# LoRaPi.net
KiCad netlist of a schematic drawn in EAGLE
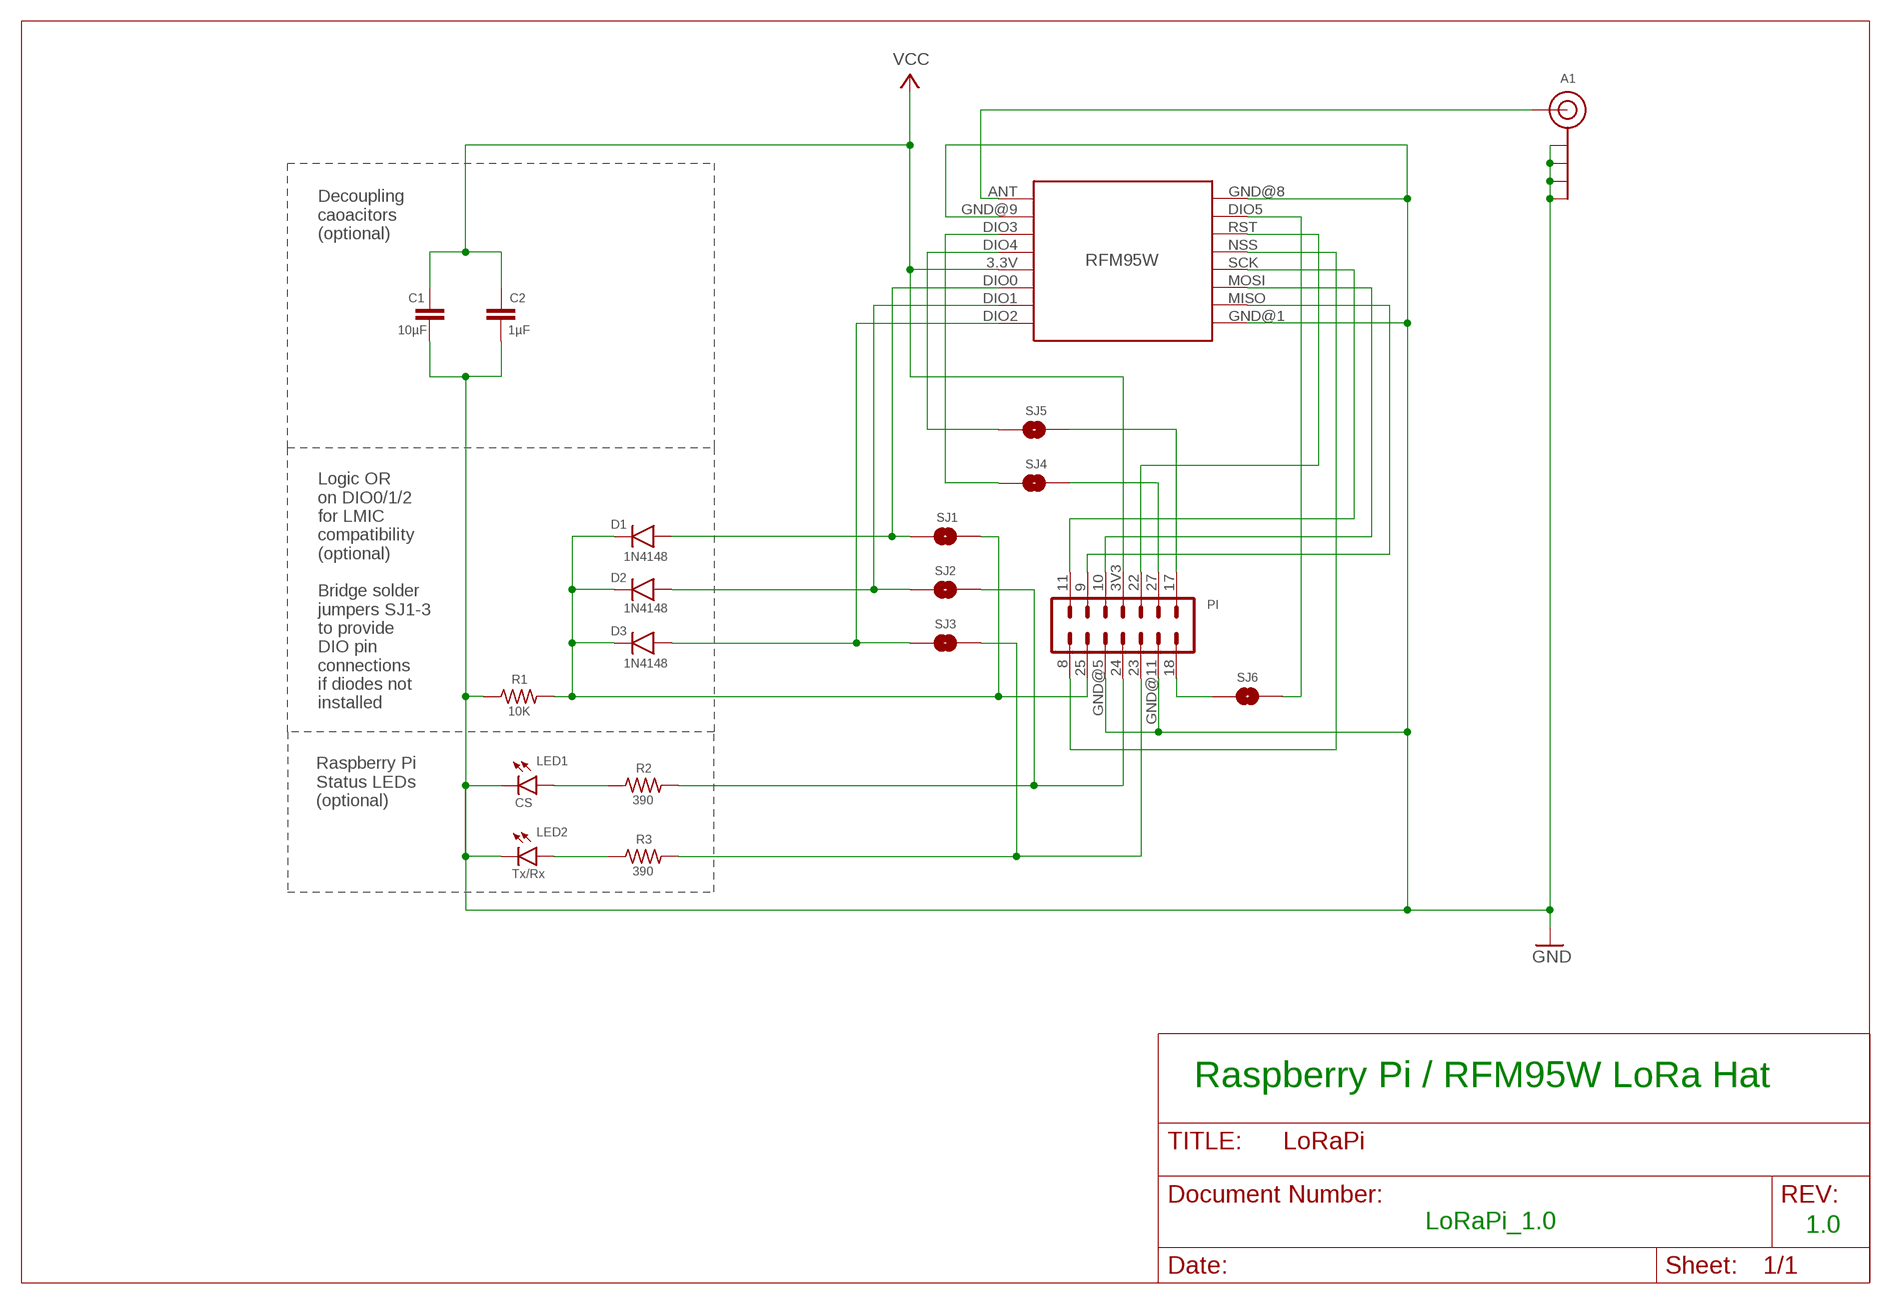
[diagram p0: schematic, sheet 1]

(export (version "E")
  (design (tool "Eeschema 10.0.6"))
  (components
    (comp (ref "A1")
      (value "U.FL-SMA-EDGE-COMBO")
      (footprint "eagle-import:U.FL-SMA-EDGE-COMBO")
      (libsource (lib "eagle-import") (part "U.FL-SMA-EDGE-COMBO"))
    )
    (comp (ref "C1")
      (value "10µF")
      (footprint "eagle-import:C0805")
      (libsource (lib "eagle-import") (part "CAPACITOR"))
    )
    (comp (ref "C2")
      (value "1µF")
      (footprint "eagle-import:C0805")
      (libsource (lib "eagle-import") (part "CAPACITOR"))
    )
    (comp (ref "D1")
      (value "1N4148")
      (footprint "eagle-import:SOD-123")
      (libsource (lib "eagle-import") (part "1N4148SMD"))
    )
    (comp (ref "D2")
      (value "1N4148")
      (footprint "eagle-import:SOD-123")
      (libsource (lib "eagle-import") (part "1N4148SMD"))
    )
    (comp (ref "D3")
      (value "1N4148")
      (footprint "eagle-import:SOD-123")
      (libsource (lib "eagle-import") (part "1N4148SMD"))
    )
    (comp (ref "LED1")
      (value "CS")
      (footprint "eagle-import:CHIP-LED0805")
      (libsource (lib "eagle-import") (part "LEDCHIP-LED0805"))
    )
    (comp (ref "LED2")
      (value "Tx/Rx")
      (footprint "eagle-import:CHIP-LED0805")
      (libsource (lib "eagle-import") (part "LEDCHIP-LED0805"))
    )
    (comp (ref "PI")
      (value "2X7-PIN-HEADER")
      (footprint "eagle-import:2X7")
      (libsource (lib "eagle-import") (part "2X7-PIN-HEADER"))
    )
    (comp (ref "R1")
      (value "10K")
      (footprint "eagle-import:R0805")
      (libsource (lib "eagle-import") (part "R-US_R0805"))
    )
    (comp (ref "R2")
      (value "390")
      (footprint "eagle-import:R0805")
      (libsource (lib "eagle-import") (part "R-US_R0805"))
    )
    (comp (ref "R3")
      (value "390")
      (footprint "eagle-import:R0805")
      (libsource (lib "eagle-import") (part "R-US_R0805"))
    )
    (comp (ref "RFM95W")
      (value "RFM95W-LORA")
      (footprint "eagle-import:RFM95W-LORA")
      (libsource (lib "eagle-import") (part "RFM95W-LORA"))
    )
    (comp (ref "SJ1") (value "SJ") (footprint "eagle-import:SJ") (libsource (lib "eagle-import") (part "SJ")))
    (comp (ref "SJ2") (value "SJ") (footprint "eagle-import:SJ") (libsource (lib "eagle-import") (part "SJ")))
    (comp (ref "SJ3") (value "SJ") (footprint "eagle-import:SJ") (libsource (lib "eagle-import") (part "SJ")))
    (comp (ref "SJ4") (value "SJ") (footprint "eagle-import:SJ") (libsource (lib "eagle-import") (part "SJ")))
    (comp (ref "SJ5") (value "SJ") (footprint "eagle-import:SJ") (libsource (lib "eagle-import") (part "SJ")))
    (comp (ref "SJ6") (value "SJ") (footprint "eagle-import:SJ") (libsource (lib "eagle-import") (part "SJ")))
  )
  (nets
    (net (code "1") (name "GND") (class "Default")
      (node (ref "A1") (pin "GND@1A") (pinfunction "GND_GND@1A") (pintype "bidirectional"))
      (node (ref "A1") (pin "GND@1B") (pinfunction "GND_GND@1B") (pintype "bidirectional"))
      (node (ref "A1") (pin "GND@2A") (pinfunction "GND_GND@2A") (pintype "bidirectional"))
      (node (ref "A1") (pin "GND@2B") (pinfunction "GND_GND@2B") (pintype "bidirectional"))
      (node (ref "C1") (pin "2") (pinfunction "2_2") (pintype "passive"))
      (node (ref "C2") (pin "2") (pinfunction "2_2") (pintype "passive"))
      (node (ref "LED1") (pin "C") (pinfunction "C_C") (pintype "passive"))
      (node (ref "LED2") (pin "C") (pinfunction "C_C") (pintype "passive"))
      (node (ref "PI") (pin "GND@11") (pinfunction "GND_GND@11") (pintype "passive"))
      (node (ref "PI") (pin "GND@5") (pinfunction "GND_GND@5") (pintype "passive"))
      (node (ref "R1") (pin "1") (pinfunction "1_1") (pintype "passive"))
      (node (ref "RFM95W") (pin "GND@1") (pinfunction "GND.1_GND@1") (pintype "power_in"))
      (node (ref "RFM95W") (pin "GND@8") (pinfunction "GND.2_GND@8") (pintype "power_in"))
      (node (ref "RFM95W") (pin "GND@9") (pinfunction "GND.3_GND@9") (pintype "power_in"))
    )
    (net (code "2") (name "Net-(A1-PadSIG)") (class "Default")
      (node (ref "A1") (pin "SIG") (pinfunction "SIG_SIG") (pintype "bidirectional"))
      (node (ref "RFM95W") (pin "ANT") (pinfunction "ANT_ANT") (pintype "passive"))
    )
    (net (code "3") (name "Net-(D1-Pad1)") (class "Default")
      (node (ref "D1") (pin "1") (pinfunction "1_1") (pintype "bidirectional"))
      (node (ref "D2") (pin "1") (pinfunction "1_1") (pintype "bidirectional"))
      (node (ref "D3") (pin "1") (pinfunction "1_1") (pintype "bidirectional"))
      (node (ref "PI") (pin "25") (pinfunction "25_25") (pintype "passive"))
      (node (ref "R1") (pin "2") (pinfunction "2_2") (pintype "passive"))
      (node (ref "SJ1") (pin "2") (pinfunction "2_2") (pintype "passive"))
    )
    (net (code "4") (name "Net-(D1-Pad2)") (class "Default")
      (node (ref "D1") (pin "2") (pinfunction "2_2") (pintype "bidirectional"))
      (node (ref "RFM95W") (pin "DIO0") (pinfunction "DIO0_DIO0") (pintype "bidirectional"))
      (node (ref "SJ1") (pin "1") (pinfunction "1_1") (pintype "passive"))
    )
    (net (code "5") (name "Net-(D2-Pad2)") (class "Default")
      (node (ref "D2") (pin "2") (pinfunction "2_2") (pintype "bidirectional"))
      (node (ref "RFM95W") (pin "DIO1") (pinfunction "DIO1_DIO1") (pintype "bidirectional"))
      (node (ref "SJ2") (pin "1") (pinfunction "1_1") (pintype "passive"))
    )
    (net (code "6") (name "Net-(D3-Pad2)") (class "Default")
      (node (ref "D3") (pin "2") (pinfunction "2_2") (pintype "bidirectional"))
      (node (ref "RFM95W") (pin "DIO2") (pinfunction "DIO2_DIO2") (pintype "bidirectional"))
      (node (ref "SJ3") (pin "1") (pinfunction "1_1") (pintype "passive"))
    )
    (net (code "7") (name "Net-(LED1-PadA)") (class "Default")
      (node (ref "LED1") (pin "A") (pinfunction "A_A") (pintype "passive"))
      (node (ref "R2") (pin "1") (pinfunction "1_1") (pintype "passive"))
    )
    (net (code "8") (name "Net-(LED2-PadA)") (class "Default")
      (node (ref "LED2") (pin "A") (pinfunction "A_A") (pintype "passive"))
      (node (ref "R3") (pin "1") (pinfunction "1_1") (pintype "passive"))
    )
    (net (code "9") (name "Net-(PI-1)") (class "Default")
      (node (ref "PI") (pin "8") (pinfunction "1_8") (pintype "passive"))
      (node (ref "RFM95W") (pin "NSS") (pinfunction "NSS_NSS") (pintype "bidirectional"))
    )
    (net (code "10") (name "Net-(PI-22)") (class "Default")
      (node (ref "PI") (pin "27") (pinfunction "22_27") (pintype "passive"))
      (node (ref "SJ4") (pin "2") (pinfunction "2_2") (pintype "passive"))
    )
    (net (code "11") (name "Net-(PI-27)") (class "Default")
      (node (ref "PI") (pin "22") (pinfunction "27_22") (pintype "passive"))
      (node (ref "RFM95W") (pin "RST") (pinfunction "RST_RST") (pintype "bidirectional"))
    )
    (net (code "12") (name "Net-(PI-Pad9)") (class "Default")
      (node (ref "PI") (pin "9") (pinfunction "9_9") (pintype "passive"))
      (node (ref "RFM95W") (pin "MISO") (pinfunction "MISO_MISO") (pintype "bidirectional"))
    )
    (net (code "13") (name "Net-(PI-Pad10)") (class "Default")
      (node (ref "PI") (pin "10") (pinfunction "10_10") (pintype "passive"))
      (node (ref "RFM95W") (pin "MOSI") (pinfunction "MOSI_MOSI") (pintype "bidirectional"))
    )
    (net (code "14") (name "Net-(PI-Pad11)") (class "Default")
      (node (ref "PI") (pin "11") (pinfunction "11_11") (pintype "passive"))
      (node (ref "RFM95W") (pin "SCK") (pinfunction "SCK_SCK") (pintype "bidirectional"))
    )
    (net (code "15") (name "Net-(PI-Pad17)") (class "Default")
      (node (ref "PI") (pin "17") (pinfunction "17_17") (pintype "passive"))
      (node (ref "SJ5") (pin "2") (pinfunction "2_2") (pintype "passive"))
    )
    (net (code "16") (name "Net-(PI-Pad18)") (class "Default")
      (node (ref "PI") (pin "18") (pinfunction "18_18") (pintype "passive"))
      (node (ref "SJ6") (pin "1") (pinfunction "1_1") (pintype "passive"))
    )
    (net (code "17") (name "Net-(PI-Pad23)") (class "Default")
      (node (ref "PI") (pin "23") (pinfunction "23_23") (pintype "passive"))
      (node (ref "R3") (pin "2") (pinfunction "2_2") (pintype "passive"))
      (node (ref "SJ3") (pin "2") (pinfunction "2_2") (pintype "passive"))
    )
    (net (code "18") (name "Net-(PI-Pad24)") (class "Default")
      (node (ref "PI") (pin "24") (pinfunction "24_24") (pintype "passive"))
      (node (ref "R2") (pin "2") (pinfunction "2_2") (pintype "passive"))
      (node (ref "SJ2") (pin "2") (pinfunction "2_2") (pintype "passive"))
    )
    (net (code "19") (name "Net-(RFM95W-PadDIO3)") (class "Default")
      (node (ref "RFM95W") (pin "DIO3") (pinfunction "DIO3_DIO3") (pintype "bidirectional"))
      (node (ref "SJ4") (pin "1") (pinfunction "1_1") (pintype "passive"))
    )
    (net (code "20") (name "Net-(RFM95W-PadDIO4)") (class "Default")
      (node (ref "RFM95W") (pin "DIO4") (pinfunction "DIO4_DIO4") (pintype "bidirectional"))
      (node (ref "SJ5") (pin "1") (pinfunction "1_1") (pintype "passive"))
    )
    (net (code "21") (name "Net-(RFM95W-PadDIO5)") (class "Default")
      (node (ref "RFM95W") (pin "DIO5") (pinfunction "DIO5_DIO5") (pintype "bidirectional"))
      (node (ref "SJ6") (pin "2") (pinfunction "2_2") (pintype "passive"))
    )
    (net (code "22") (name "VCC") (class "Default")
      (node (ref "C1") (pin "1") (pinfunction "1_1") (pintype "passive"))
      (node (ref "C2") (pin "1") (pinfunction "1_1") (pintype "passive"))
      (node (ref "PI") (pin "3V3") (pinfunction "3V3_3V3") (pintype "passive"))
      (node (ref "RFM95W") (pin "3.3V") (pinfunction "3.3V_3.3V") (pintype "power_in"))
    )
  )
)
